# MotorDriver2.net
KiCad netlist of a schematic drawn in Altium Designer
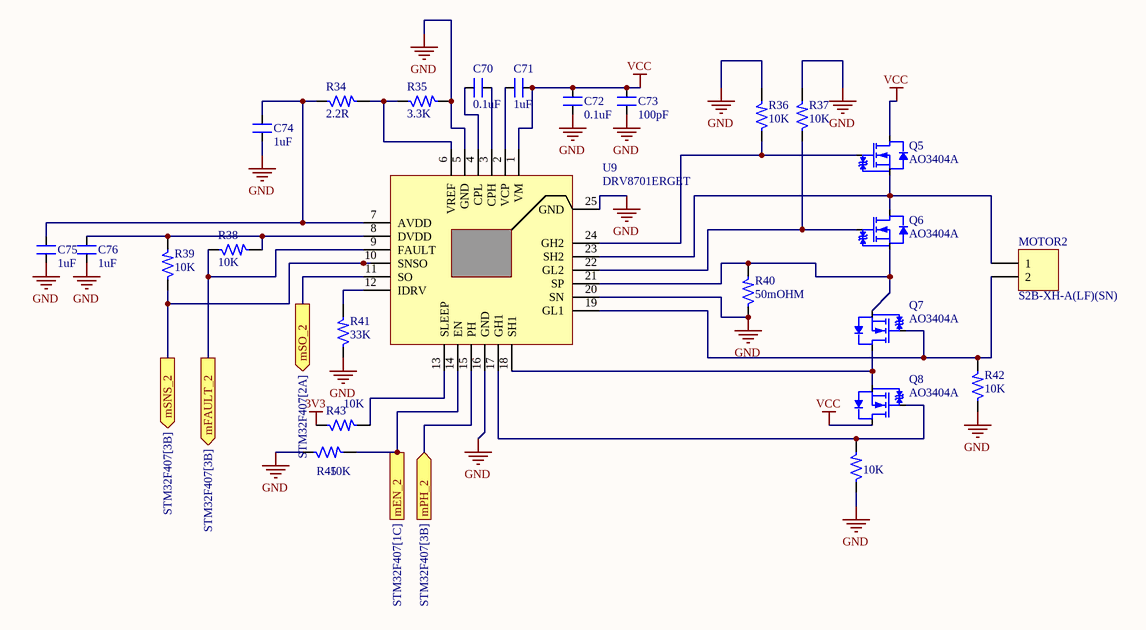
[diagram p0: MotorDriver2.SchDoc]

(export (version "E")
  (design (tool "Eeschema 10.0.6"))
  (components
    (comp (ref "C70")
      (value "0.1uF")
      (footprint "CAP_0805")
      (description "0.1µF ±20% 50V Ceramic Capacitor X7R 0805 (2012 Metric)")
      (fields
        (field (name "MANUFACTURER") "Samsung Electro-Mechanics")
        (field (name "MANUFACTURER PART NUMBER") "CL21B104MBCNNNC")
      )
      (libsource (lib "ESTEEMPCBLIB") (part "CAP_0.1uF-50V-20%-0805"))
    )
    (comp (ref "C71")
      (value "1uF")
      (footprint "CAP_0805")
      (description "1µF ±5% 50V Ceramic Capacitor X7R 0805 (2012 Metric)")
      (fields
        (field (name "MANUFACTURER") "Samsung")
        (field (name "MANUFACTURER PART NUMBER") "CC0805JKX7R9BB105")
      )
      (libsource (lib "ESTEEMPCBLIB") (part "CAP_1uF-50V-5%-0805"))
    )
    (comp (ref "C72")
      (value "0.1uF")
      (footprint "CAP_0805")
      (description "0.1µF ±20% 50V Ceramic Capacitor X7R 0805 (2012 Metric)")
      (fields
        (field (name "MANUFACTURER") "Samsung Electro-Mechanics")
        (field (name "MANUFACTURER PART NUMBER") "CL21B104MBCNNNC")
      )
      (libsource (lib "ESTEEMPCBLIB") (part "CAP_0.1uF-50V-20%-0805"))
    )
    (comp (ref "C73")
      (value "100pF")
      (footprint "CAP_0805")
      (description "100pF ±5% 100V Ceramic Capacitor C0G, NP0 0805 (2012 Metric)")
      (fields
        (field (name "MANUFACTURER") "Murata")
        (field (name "MANUFACTURER PART NUMBER") "CL21C101JC61PNC")
      )
      (libsource (lib "ESTEEMPCBLIB") (part "CAP_100pF-100V-5%-0805"))
    )
    (comp (ref "C74")
      (value "1uF")
      (footprint "CAP_0805")
      (description "1µF ±5% 50V Ceramic Capacitor X7R 0805 (2012 Metric)")
      (fields
        (field (name "MANUFACTURER") "Samsung")
        (field (name "MANUFACTURER PART NUMBER") "CC0805JKX7R9BB105")
      )
      (libsource (lib "ESTEEMPCBLIB") (part "CAP_1uF-50V-5%-0805"))
    )
    (comp (ref "C75")
      (value "1uF")
      (footprint "CAP_0805")
      (description "1µF ±5% 50V Ceramic Capacitor X7R 0805 (2012 Metric)")
      (fields
        (field (name "MANUFACTURER") "Samsung")
        (field (name "MANUFACTURER PART NUMBER") "CC0805JKX7R9BB105")
      )
      (libsource (lib "ESTEEMPCBLIB") (part "CAP_1uF-50V-5%-0805"))
    )
    (comp (ref "C76")
      (value "1uF")
      (footprint "CAP_0805")
      (description "1µF ±5% 50V Ceramic Capacitor X7R 0805 (2012 Metric)")
      (fields
        (field (name "MANUFACTURER") "Samsung")
        (field (name "MANUFACTURER PART NUMBER") "CC0805JKX7R9BB105")
      )
      (libsource (lib "ESTEEMPCBLIB") (part "CAP_1uF-50V-5%-0805"))
    )
    (comp (ref "MOTOR2")
      (value "S2B-XH-A(LF)(SN)")
      (footprint "CON2_100_S2B-XH-A_TH_RA")
      (description "2 Pins, 1 Row 2.54mm Pitch, right angle Connector, male")
      (fields (field (name "MANUFACTURER") "JST") (field (name "MATING PART NUMBER") "XHP-2"))
      (libsource (lib "ESTEEMPCBLIB") (part "CON-PLG_2X1-100-RA-TH"))
    )
    (comp (ref "Q5")
      (value "AO3404A")
      (footprint "SOT 23-3")
      (description "N-Channel 30V 5.8A (Ta) 1.4W (Ta) Surface Mount SOT-23-3L")
      (fields (field (name "MANUFACTURER") "International Rectifier"))
      (libsource (lib "ESTEEMPCBLIB") (part "MOSFET-N_30V-5.8A-SOT23"))
    )
    (comp (ref "Q6")
      (value "AO3404A")
      (footprint "SOT 23-3")
      (description "N-Channel 30V 5.8A (Ta) 1.4W (Ta) Surface Mount SOT-23-3L")
      (fields (field (name "MANUFACTURER") "International Rectifier"))
      (libsource (lib "ESTEEMPCBLIB") (part "MOSFET-N_30V-5.8A-SOT23"))
    )
    (comp (ref "Q7")
      (value "AO3404A")
      (footprint "SOT 23-3")
      (description "N-Channel 30V 5.8A (Ta) 1.4W (Ta) Surface Mount SOT-23-3L")
      (fields (field (name "MANUFACTURER") "International Rectifier"))
      (libsource (lib "ESTEEMPCBLIB") (part "MOSFET-N_30V-5.8A-SOT23"))
    )
    (comp (ref "Q8")
      (value "AO3404A")
      (footprint "SOT 23-3")
      (description "N-Channel 30V 5.8A (Ta) 1.4W (Ta) Surface Mount SOT-23-3L")
      (fields (field (name "MANUFACTURER") "International Rectifier"))
      (libsource (lib "ESTEEMPCBLIB") (part "MOSFET-N_30V-5.8A-SOT23"))
    )
    (comp (ref "R34")
      (value "2.2R")
      (footprint "RES_0603")
      (fields
        (field (name "MANUFACTURER") "Panasonic Electronic Components")
        (field (name "MANUFACTURER PART NUMBER") "ERJ-3RQF2R2V")
      )
      (libsource (lib "ESTEEMPCBLIB") (part "RES_2.2R-0.1W-1%-0603"))
    )
    (comp (ref "R35")
      (value "3.3K")
      (footprint "RES_0805")
      (description "3.3 kOhms ±1% 0.125W, 1/8W Chip Resistor 0805 (2012 Metric) Thick Film")
      (fields (field (name "MANUFACTURER") "Panasonic") (field (name "MANUFACTURER PART NUMBER") "1623214-1"))
      (libsource (lib "ESTEEMPCBLIB") (part "RES_3.3K-0.125W-1%-0805"))
    )
    (comp (ref "R36")
      (value "10K")
      (footprint "RES_0805")
      (description "10 kOhms ±1% 0.125W, 1/8W Chip Resistor 0805 (2012 Metric) Automotive AEC-Q200 Thick Film")
      (fields (field (name "MANUFACTURER") "CTS") (field (name "MANUFACTURER PART NUMBER") "WR08X1002FTL"))
      (libsource (lib "ESTEEMPCBLIB") (part "RES_10K-0.125W-1%-0805"))
    )
    (comp (ref "R37")
      (value "10K")
      (footprint "RES_0805")
      (description "10 kOhms ±1% 0.125W, 1/8W Chip Resistor 0805 (2012 Metric) Automotive AEC-Q200 Thick Film")
      (fields (field (name "MANUFACTURER") "CTS") (field (name "MANUFACTURER PART NUMBER") "WR08X1002FTL"))
      (libsource (lib "ESTEEMPCBLIB") (part "RES_10K-0.125W-1%-0805"))
    )
    (comp (ref "R38")
      (value "10K")
      (footprint "RES_0805")
      (description "10 kOhms ±1% 0.125W, 1/8W Chip Resistor 0805 (2012 Metric) Automotive AEC-Q200 Thick Film")
      (fields (field (name "MANUFACTURER") "CTS") (field (name "MANUFACTURER PART NUMBER") "WR08X1002FTL"))
      (libsource (lib "ESTEEMPCBLIB") (part "RES_10K-0.125W-1%-0805"))
    )
    (comp (ref "R39")
      (value "10K")
      (footprint "RES_0805")
      (description "10 kOhms ±1% 0.125W, 1/8W Chip Resistor 0805 (2012 Metric) Automotive AEC-Q200 Thick Film")
      (fields (field (name "MANUFACTURER") "CTS") (field (name "MANUFACTURER PART NUMBER") "WR08X1002FTL"))
      (libsource (lib "ESTEEMPCBLIB") (part "RES_10K-0.125W-1%-0805"))
    )
    (comp (ref "R40")
      (value "50mOHM")
      (footprint "RES_2512")
      (fields
        (field (name "MANUFACTURER") "Yageo")
        (field (name "MANUFACTURER PART NUMBER") "PA2512FKF7W0R05E")
      )
      (libsource (lib "ESTEEMPCBLIB") (part "RES_50mOhm-2W-1%-2512"))
    )
    (comp (ref "R41")
      (value "33K")
      (footprint "RES_0805")
      (fields
        (field (name "MANUFACTURER") "Vishay BCcomponents")
        (field (name "MANUFACTURER PART NUMBER") "CRG0805F33K")
      )
      (libsource (lib "ESTEEMPCBLIB") (part "RES_33K-0.125W-1%-0805"))
    )
    (comp (ref "R42")
      (value "10K")
      (footprint "RES_0805")
      (description "10 kOhms ±1% 0.125W, 1/8W Chip Resistor 0805 (2012 Metric) Automotive AEC-Q200 Thick Film")
      (fields (field (name "MANUFACTURER") "CTS") (field (name "MANUFACTURER PART NUMBER") "WR08X1002FTL"))
      (libsource (lib "ESTEEMPCBLIB") (part "RES_10K-0.125W-1%-0805"))
    )
    (comp (ref "R43")
      (value "10K")
      (footprint "RES_0805")
      (description "10 kOhms ±1% 0.125W, 1/8W Chip Resistor 0805 (2012 Metric) Automotive AEC-Q200 Thick Film")
      (fields (field (name "MANUFACTURER") "CTS") (field (name "MANUFACTURER PART NUMBER") "WR08X1002FTL"))
      (libsource (lib "ESTEEMPCBLIB") (part "RES_10K-0.125W-1%-0805"))
    )
    (comp (ref "R44")
      (value "10K")
      (footprint "RES_0805")
      (description "10 kOhms ±1% 0.125W, 1/8W Chip Resistor 0805 (2012 Metric) Automotive AEC-Q200 Thick Film")
      (fields (field (name "MANUFACTURER") "CTS") (field (name "MANUFACTURER PART NUMBER") "WR08X1002FTL"))
      (libsource (lib "ESTEEMPCBLIB") (part "RES_10K-0.125W-1%-0805"))
    )
    (comp (ref "R45")
      (value "10K")
      (footprint "RES_0805")
      (description "10 kOhms ±1% 0.125W, 1/8W Chip Resistor 0805 (2012 Metric) Automotive AEC-Q200 Thick Film")
      (fields (field (name "MANUFACTURER") "CTS") (field (name "MANUFACTURER PART NUMBER") "WR08X1002FTL"))
      (libsource (lib "ESTEEMPCBLIB") (part "RES_10K-0.125W-1%-0805"))
    )
    (comp (ref "U9")
      (value "DRV8701ERGET")
      (footprint "VFQFN24_19.6_196_12X32_SMD_1")
      (description "Motor Driver Power MOSFET Parallel 24-VQFN (4x4)")
      (fields (field (name "MANUFACTURER") "Texas Instruments"))
      (libsource (lib "ESTEEMPCBLIB") (part "IC_DRV8701ERGET"))
    )
  )
  (nets
    (net (code "1") (name "/mEN_2") (class "Default")
      (node (ref "R45") (pin "2") (pinfunction "2_2") (pintype "passive"))
      (node (ref "U9") (pin "14") (pinfunction "EN_14") (pintype "passive"))
    )
    (net (code "2") (name "/mFAULT_2") (class "Default")
      (node (ref "R38") (pin "1") (pinfunction "1_1") (pintype "passive"))
      (node (ref "U9") (pin "9") (pinfunction "FAULT_9") (pintype "passive"))
    )
    (net (code "3") (name "/mPH_2") (class "Default")
      (node (ref "U9") (pin "15") (pinfunction "PH_15") (pintype "passive"))
    )
    (net (code "4") (name "/mSNS_2") (class "Default")
      (node (ref "R39") (pin "1") (pinfunction "1_1") (pintype "passive"))
      (node (ref "U9") (pin "10") (pinfunction "SNSO_10") (pintype "passive"))
    )
    (net (code "5") (name "/mSO_2") (class "Default")
      (node (ref "U9") (pin "11") (pinfunction "SO_11") (pintype "passive"))
    )
    (net (code "6") (name "3V3") (class "Default")
      (node (ref "R43") (pin "1") (pinfunction "1_1") (pintype "passive"))
    )
    (net (code "7") (name "GND") (class "Default")
      (node (ref "C72") (pin "1") (pinfunction "1_1") (pintype "passive"))
      (node (ref "C73") (pin "1") (pinfunction "1_1") (pintype "passive"))
      (node (ref "C74") (pin "1") (pinfunction "1_1") (pintype "passive"))
      (node (ref "C75") (pin "1") (pinfunction "1_1") (pintype "passive"))
      (node (ref "C76") (pin "1") (pinfunction "1_1") (pintype "passive"))
      (node (ref "R35") (pin "2") (pinfunction "2_2") (pintype "passive"))
      (node (ref "R36") (pin "2") (pinfunction "2_2") (pintype "passive"))
      (node (ref "R37") (pin "2") (pinfunction "2_2") (pintype "passive"))
      (node (ref "R40") (pin "1") (pinfunction "1_1") (pintype "passive"))
      (node (ref "R41") (pin "1") (pinfunction "1_1") (pintype "passive"))
      (node (ref "R42") (pin "1") (pinfunction "1_1") (pintype "passive"))
      (node (ref "R44") (pin "1") (pinfunction "1_1") (pintype "passive"))
      (node (ref "R45") (pin "1") (pinfunction "1_1") (pintype "passive"))
      (node (ref "U9") (pin "16") (pinfunction "GND_16") (pintype "passive"))
      (node (ref "U9") (pin "20") (pinfunction "SN_20") (pintype "passive"))
      (node (ref "U9") (pin "25") (pinfunction "GND_25") (pintype "passive"))
      (node (ref "U9") (pin "5") (pinfunction "GND_5") (pintype "passive"))
    )
    (net (code "8") (name "Net-(Q5-G)") (class "Default")
      (node (ref "Q5") (pin "1") (pinfunction "G_1") (pintype "passive"))
      (node (ref "R36") (pin "1") (pinfunction "1_1") (pintype "passive"))
      (node (ref "U9") (pin "24") (pinfunction "GH2_24") (pintype "passive"))
    )
    (net (code "9") (name "Net-(Q5-S)") (class "Default")
      (node (ref "MOTOR2") (pin "1") (pinfunction "1_1") (pintype "passive"))
      (node (ref "Q5") (pin "2") (pinfunction "S_2") (pintype "passive"))
      (node (ref "Q6") (pin "3") (pinfunction "D_3") (pintype "passive"))
      (node (ref "U9") (pin "23") (pinfunction "SH2_23") (pintype "passive"))
    )
    (net (code "10") (name "Net-(Q6-G)") (class "Default")
      (node (ref "Q6") (pin "1") (pinfunction "G_1") (pintype "passive"))
      (node (ref "R37") (pin "1") (pinfunction "1_1") (pintype "passive"))
      (node (ref "U9") (pin "22") (pinfunction "GL2_22") (pintype "passive"))
    )
    (net (code "11") (name "Net-(Q6-S)") (class "Default")
      (node (ref "Q6") (pin "2") (pinfunction "S_2") (pintype "passive"))
      (node (ref "Q7") (pin "2") (pinfunction "S_2") (pintype "passive"))
      (node (ref "R40") (pin "2") (pinfunction "2_2") (pintype "passive"))
      (node (ref "U9") (pin "21") (pinfunction "SP_21") (pintype "passive"))
    )
    (net (code "12") (name "Net-(Q7-D)") (class "Default")
      (node (ref "Q7") (pin "3") (pinfunction "D_3") (pintype "passive"))
      (node (ref "Q8") (pin "2") (pinfunction "S_2") (pintype "passive"))
      (node (ref "U9") (pin "18") (pinfunction "SH1_18") (pintype "passive"))
    )
    (net (code "13") (name "Net-(Q7-G)") (class "Default")
      (node (ref "MOTOR2") (pin "2") (pinfunction "2_2") (pintype "passive"))
      (node (ref "Q7") (pin "1") (pinfunction "G_1") (pintype "passive"))
      (node (ref "R42") (pin "2") (pinfunction "2_2") (pintype "passive"))
      (node (ref "U9") (pin "19") (pinfunction "GL1_19") (pintype "passive"))
    )
    (net (code "14") (name "Net-(Q8-G)") (class "Default")
      (node (ref "Q8") (pin "1") (pinfunction "G_1") (pintype "passive"))
      (node (ref "R44") (pin "2") (pinfunction "2_2") (pintype "passive"))
      (node (ref "U9") (pin "17") (pinfunction "GH1_17") (pintype "passive"))
    )
    (net (code "15") (name "Net-(U9-AVDD)") (class "Default")
      (node (ref "C74") (pin "2") (pinfunction "2_2") (pintype "passive"))
      (node (ref "C75") (pin "2") (pinfunction "2_2") (pintype "passive"))
      (node (ref "R34") (pin "1") (pinfunction "1_1") (pintype "passive"))
      (node (ref "U9") (pin "7") (pinfunction "AVDD_7") (pintype "passive"))
    )
    (net (code "16") (name "Net-(U9-CPH)") (class "Default")
      (node (ref "C70") (pin "1") (pinfunction "1_1") (pintype "passive"))
      (node (ref "U9") (pin "3") (pinfunction "CPH_3") (pintype "passive"))
    )
    (net (code "17") (name "Net-(U9-CPL)") (class "Default")
      (node (ref "C70") (pin "2") (pinfunction "2_2") (pintype "passive"))
      (node (ref "U9") (pin "4") (pinfunction "CPL_4") (pintype "passive"))
    )
    (net (code "18") (name "Net-(U9-DVDD)") (class "Default")
      (node (ref "C76") (pin "2") (pinfunction "2_2") (pintype "passive"))
      (node (ref "R38") (pin "2") (pinfunction "2_2") (pintype "passive"))
      (node (ref "R39") (pin "2") (pinfunction "2_2") (pintype "passive"))
      (node (ref "U9") (pin "8") (pinfunction "DVDD_8") (pintype "passive"))
    )
    (net (code "19") (name "Net-(U9-IDRV)") (class "Default")
      (node (ref "R41") (pin "2") (pinfunction "2_2") (pintype "passive"))
      (node (ref "U9") (pin "12") (pinfunction "IDRV_12") (pintype "passive"))
    )
    (net (code "20") (name "Net-(U9-SLEEP)") (class "Default")
      (node (ref "R43") (pin "2") (pinfunction "2_2") (pintype "passive"))
      (node (ref "U9") (pin "13") (pinfunction "SLEEP_13") (pintype "passive"))
    )
    (net (code "21") (name "Net-(U9-VCP)") (class "Default")
      (node (ref "C71") (pin "2") (pinfunction "2_2") (pintype "passive"))
      (node (ref "U9") (pin "2") (pinfunction "VCP_2") (pintype "passive"))
    )
    (net (code "22") (name "Net-(U9-VREF)") (class "Default")
      (node (ref "R34") (pin "2") (pinfunction "2_2") (pintype "passive"))
      (node (ref "R35") (pin "1") (pinfunction "1_1") (pintype "passive"))
      (node (ref "U9") (pin "6") (pinfunction "VREF_6") (pintype "passive"))
    )
    (net (code "23") (name "VCC") (class "Default")
      (node (ref "C71") (pin "1") (pinfunction "1_1") (pintype "passive"))
      (node (ref "C72") (pin "2") (pinfunction "2_2") (pintype "passive"))
      (node (ref "C73") (pin "2") (pinfunction "2_2") (pintype "passive"))
      (node (ref "Q5") (pin "3") (pinfunction "D_3") (pintype "passive"))
      (node (ref "Q8") (pin "3") (pinfunction "D_3") (pintype "passive"))
      (node (ref "U9") (pin "1") (pinfunction "VM_1") (pintype "passive"))
    )
  )
)
